# barometer.net
KiCad netlist of a schematic drawn in EAGLE
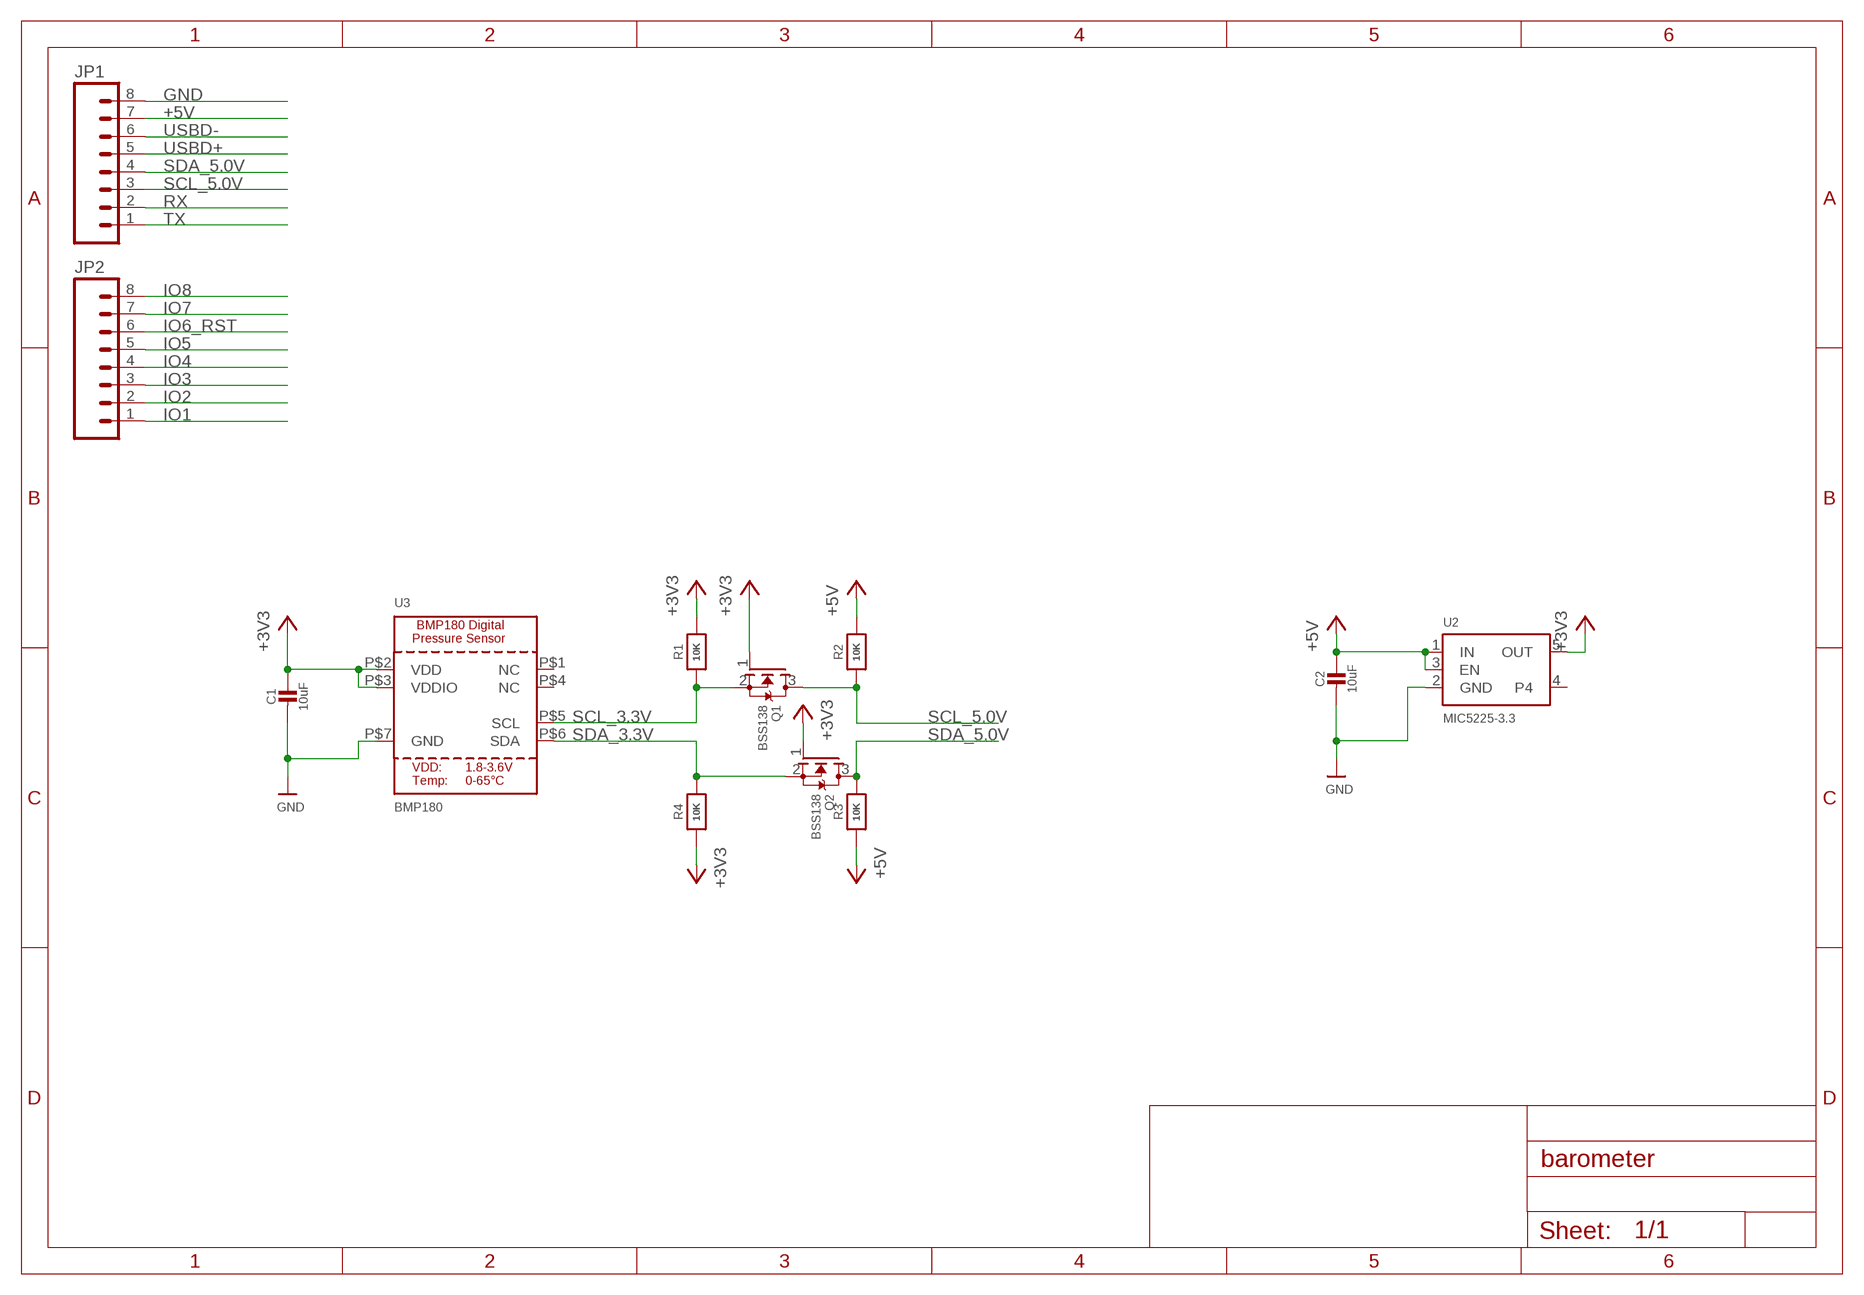
[diagram p0: schematic, sheet 1]

(export (version "E")
  (design (tool "Eeschema 10.0.6"))
  (components
    (comp (ref "C1")
      (value "10uF")
      (footprint "eagle-import:0805-NO")
      (libsource (lib "eagle-import") (part "CAP_CERAMIC0805-NOOUTLINE"))
    )
    (comp (ref "C2")
      (value "10uF")
      (footprint "eagle-import:0805-NO")
      (libsource (lib "eagle-import") (part "CAP_CERAMIC0805-NOOUTLINE"))
    )
    (comp (ref "JP1")
      (value "M081X08")
      (footprint "eagle-import:1X08")
      (libsource (lib "eagle-import") (part "M081X08"))
    )
    (comp (ref "JP2")
      (value "M081X08")
      (footprint "eagle-import:1X08")
      (libsource (lib "eagle-import") (part "M081X08"))
    )
    (comp (ref "Q1")
      (value "BSS138")
      (footprint "eagle-import:SOT23")
      (libsource (lib "eagle-import") (part "MOSFET-NREFLOW"))
    )
    (comp (ref "Q2")
      (value "BSS138")
      (footprint "eagle-import:SOT23")
      (libsource (lib "eagle-import") (part "MOSFET-NREFLOW"))
    )
    (comp (ref "R1")
      (value "10K")
      (footprint "eagle-import:0805-NO")
      (libsource (lib "eagle-import") (part "RESISTOR0805_NOOUTLINE"))
    )
    (comp (ref "R2")
      (value "10K")
      (footprint "eagle-import:_0805MP")
      (libsource (lib "eagle-import") (part "RESISTOR_0805MP"))
    )
    (comp (ref "R3")
      (value "10K")
      (footprint "eagle-import:0805-NO")
      (libsource (lib "eagle-import") (part "RESISTOR0805_NOOUTLINE"))
    )
    (comp (ref "R4")
      (value "10K")
      (footprint "eagle-import:0805-NO")
      (libsource (lib "eagle-import") (part "RESISTOR0805_NOOUTLINE"))
    )
    (comp (ref "U2")
      (value "MIC5225-3.3")
      (footprint "eagle-import:SOT23-5")
      (libsource (lib "eagle-import") (part "VREG_SOT23-5"))
    )
    (comp (ref "U3")
      (value "BMP180")
      (footprint "eagle-import:BMP180_EXTENDED")
      (libsource (lib "eagle-import") (part "BMP180EXT"))
    )
  )
  (nets
    (net (code "1") (name "+3V3") (class "Default")
      (node (ref "C1") (pin "1") (pinfunction "1_1") (pintype "passive"))
      (node (ref "Q1") (pin "1") (pinfunction "G_1") (pintype "bidirectional"))
      (node (ref "Q2") (pin "1") (pinfunction "G_1") (pintype "bidirectional"))
      (node (ref "R1") (pin "2") (pinfunction "2_2") (pintype "passive"))
      (node (ref "R4") (pin "1") (pinfunction "1_1") (pintype "passive"))
      (node (ref "U2") (pin "5") (pinfunction "OUT_5") (pintype "power_in"))
      (node (ref "U3") (pin "P$2") (pinfunction "VDD_P$2") (pintype "power_in"))
      (node (ref "U3") (pin "P$3") (pinfunction "VDDIO_P$3") (pintype "power_in"))
    )
    (net (code "2") (name "+5V") (class "Default")
      (node (ref "C2") (pin "1") (pinfunction "1_1") (pintype "passive"))
      (node (ref "JP1") (pin "7") (pinfunction "7_7") (pintype "passive"))
      (node (ref "R2") (pin "2") (pinfunction "2_2") (pintype "passive"))
      (node (ref "R3") (pin "1") (pinfunction "1_1") (pintype "passive"))
      (node (ref "U2") (pin "1") (pinfunction "IN_1") (pintype "power_in"))
      (node (ref "U2") (pin "3") (pinfunction "EN_3") (pintype "input"))
    )
    (net (code "3") (name "/IO1") (class "Default")
      (node (ref "JP2") (pin "1") (pinfunction "1_1") (pintype "passive"))
    )
    (net (code "4") (name "/IO2") (class "Default")
      (node (ref "JP2") (pin "2") (pinfunction "2_2") (pintype "passive"))
    )
    (net (code "5") (name "/IO3") (class "Default")
      (node (ref "JP2") (pin "3") (pinfunction "3_3") (pintype "passive"))
    )
    (net (code "6") (name "/IO4") (class "Default")
      (node (ref "JP2") (pin "4") (pinfunction "4_4") (pintype "passive"))
    )
    (net (code "7") (name "/IO5") (class "Default")
      (node (ref "JP2") (pin "5") (pinfunction "5_5") (pintype "passive"))
    )
    (net (code "8") (name "/IO6_RST") (class "Default")
      (node (ref "JP2") (pin "6") (pinfunction "6_6") (pintype "passive"))
    )
    (net (code "9") (name "/IO7") (class "Default")
      (node (ref "JP2") (pin "7") (pinfunction "7_7") (pintype "passive"))
    )
    (net (code "10") (name "/IO8") (class "Default")
      (node (ref "JP2") (pin "8") (pinfunction "8_8") (pintype "passive"))
    )
    (net (code "11") (name "/RX") (class "Default")
      (node (ref "JP1") (pin "2") (pinfunction "2_2") (pintype "passive"))
    )
    (net (code "12") (name "/SCL_3.3V") (class "Default")
      (node (ref "Q1") (pin "2") (pinfunction "S_2") (pintype "bidirectional"))
      (node (ref "R1") (pin "1") (pinfunction "1_1") (pintype "passive"))
      (node (ref "U3") (pin "P$5") (pinfunction "SCL_P$5") (pintype "bidirectional"))
    )
    (net (code "13") (name "/SCL_5.0V") (class "Default")
      (node (ref "JP1") (pin "3") (pinfunction "3_3") (pintype "passive"))
      (node (ref "Q1") (pin "3") (pinfunction "D_3") (pintype "bidirectional"))
      (node (ref "R2") (pin "1") (pinfunction "1_1") (pintype "passive"))
    )
    (net (code "14") (name "/SDA_3.3V") (class "Default")
      (node (ref "Q2") (pin "2") (pinfunction "S_2") (pintype "bidirectional"))
      (node (ref "R4") (pin "2") (pinfunction "2_2") (pintype "passive"))
      (node (ref "U3") (pin "P$6") (pinfunction "SDA_P$6") (pintype "bidirectional"))
    )
    (net (code "15") (name "/SDA_5.0V") (class "Default")
      (node (ref "JP1") (pin "4") (pinfunction "4_4") (pintype "passive"))
      (node (ref "Q2") (pin "3") (pinfunction "D_3") (pintype "bidirectional"))
      (node (ref "R3") (pin "2") (pinfunction "2_2") (pintype "passive"))
    )
    (net (code "16") (name "/TX") (class "Default")
      (node (ref "JP1") (pin "1") (pinfunction "1_1") (pintype "passive"))
    )
    (net (code "17") (name "/USBD+") (class "Default")
      (node (ref "JP1") (pin "5") (pinfunction "5_5") (pintype "passive"))
    )
    (net (code "18") (name "/USBD-") (class "Default")
      (node (ref "JP1") (pin "6") (pinfunction "6_6") (pintype "passive"))
    )
    (net (code "19") (name "GND") (class "Default")
      (node (ref "C1") (pin "2") (pinfunction "2_2") (pintype "passive"))
      (node (ref "C2") (pin "2") (pinfunction "2_2") (pintype "passive"))
      (node (ref "JP1") (pin "8") (pinfunction "8_8") (pintype "passive"))
      (node (ref "U2") (pin "2") (pinfunction "GND_2") (pintype "power_in"))
      (node (ref "U3") (pin "P$7") (pinfunction "GND_P$7") (pintype "power_in"))
    )
    (net (code "20") (name "unconnected-(U2-P4-Pad4)") (class "Default")
      (node (ref "U2") (pin "4") (pinfunction "P4_4") (pintype "bidirectional"))
    )
    (net (code "21") (name "unconnected-(U3-NC-PadP$1)") (class "Default")
      (node (ref "U3") (pin "P$1") (pinfunction "NC_P$1") (pintype "no_connect"))
    )
    (net (code "22") (name "unconnected-(U3-NC-PadP$4)") (class "Default")
      (node (ref "U3") (pin "P$4") (pinfunction "NC_P$4") (pintype "no_connect"))
    )
  )
)
